# LPCB227_-_OVERVIEW.net
KiCad netlist of a schematic drawn in Altium Designer
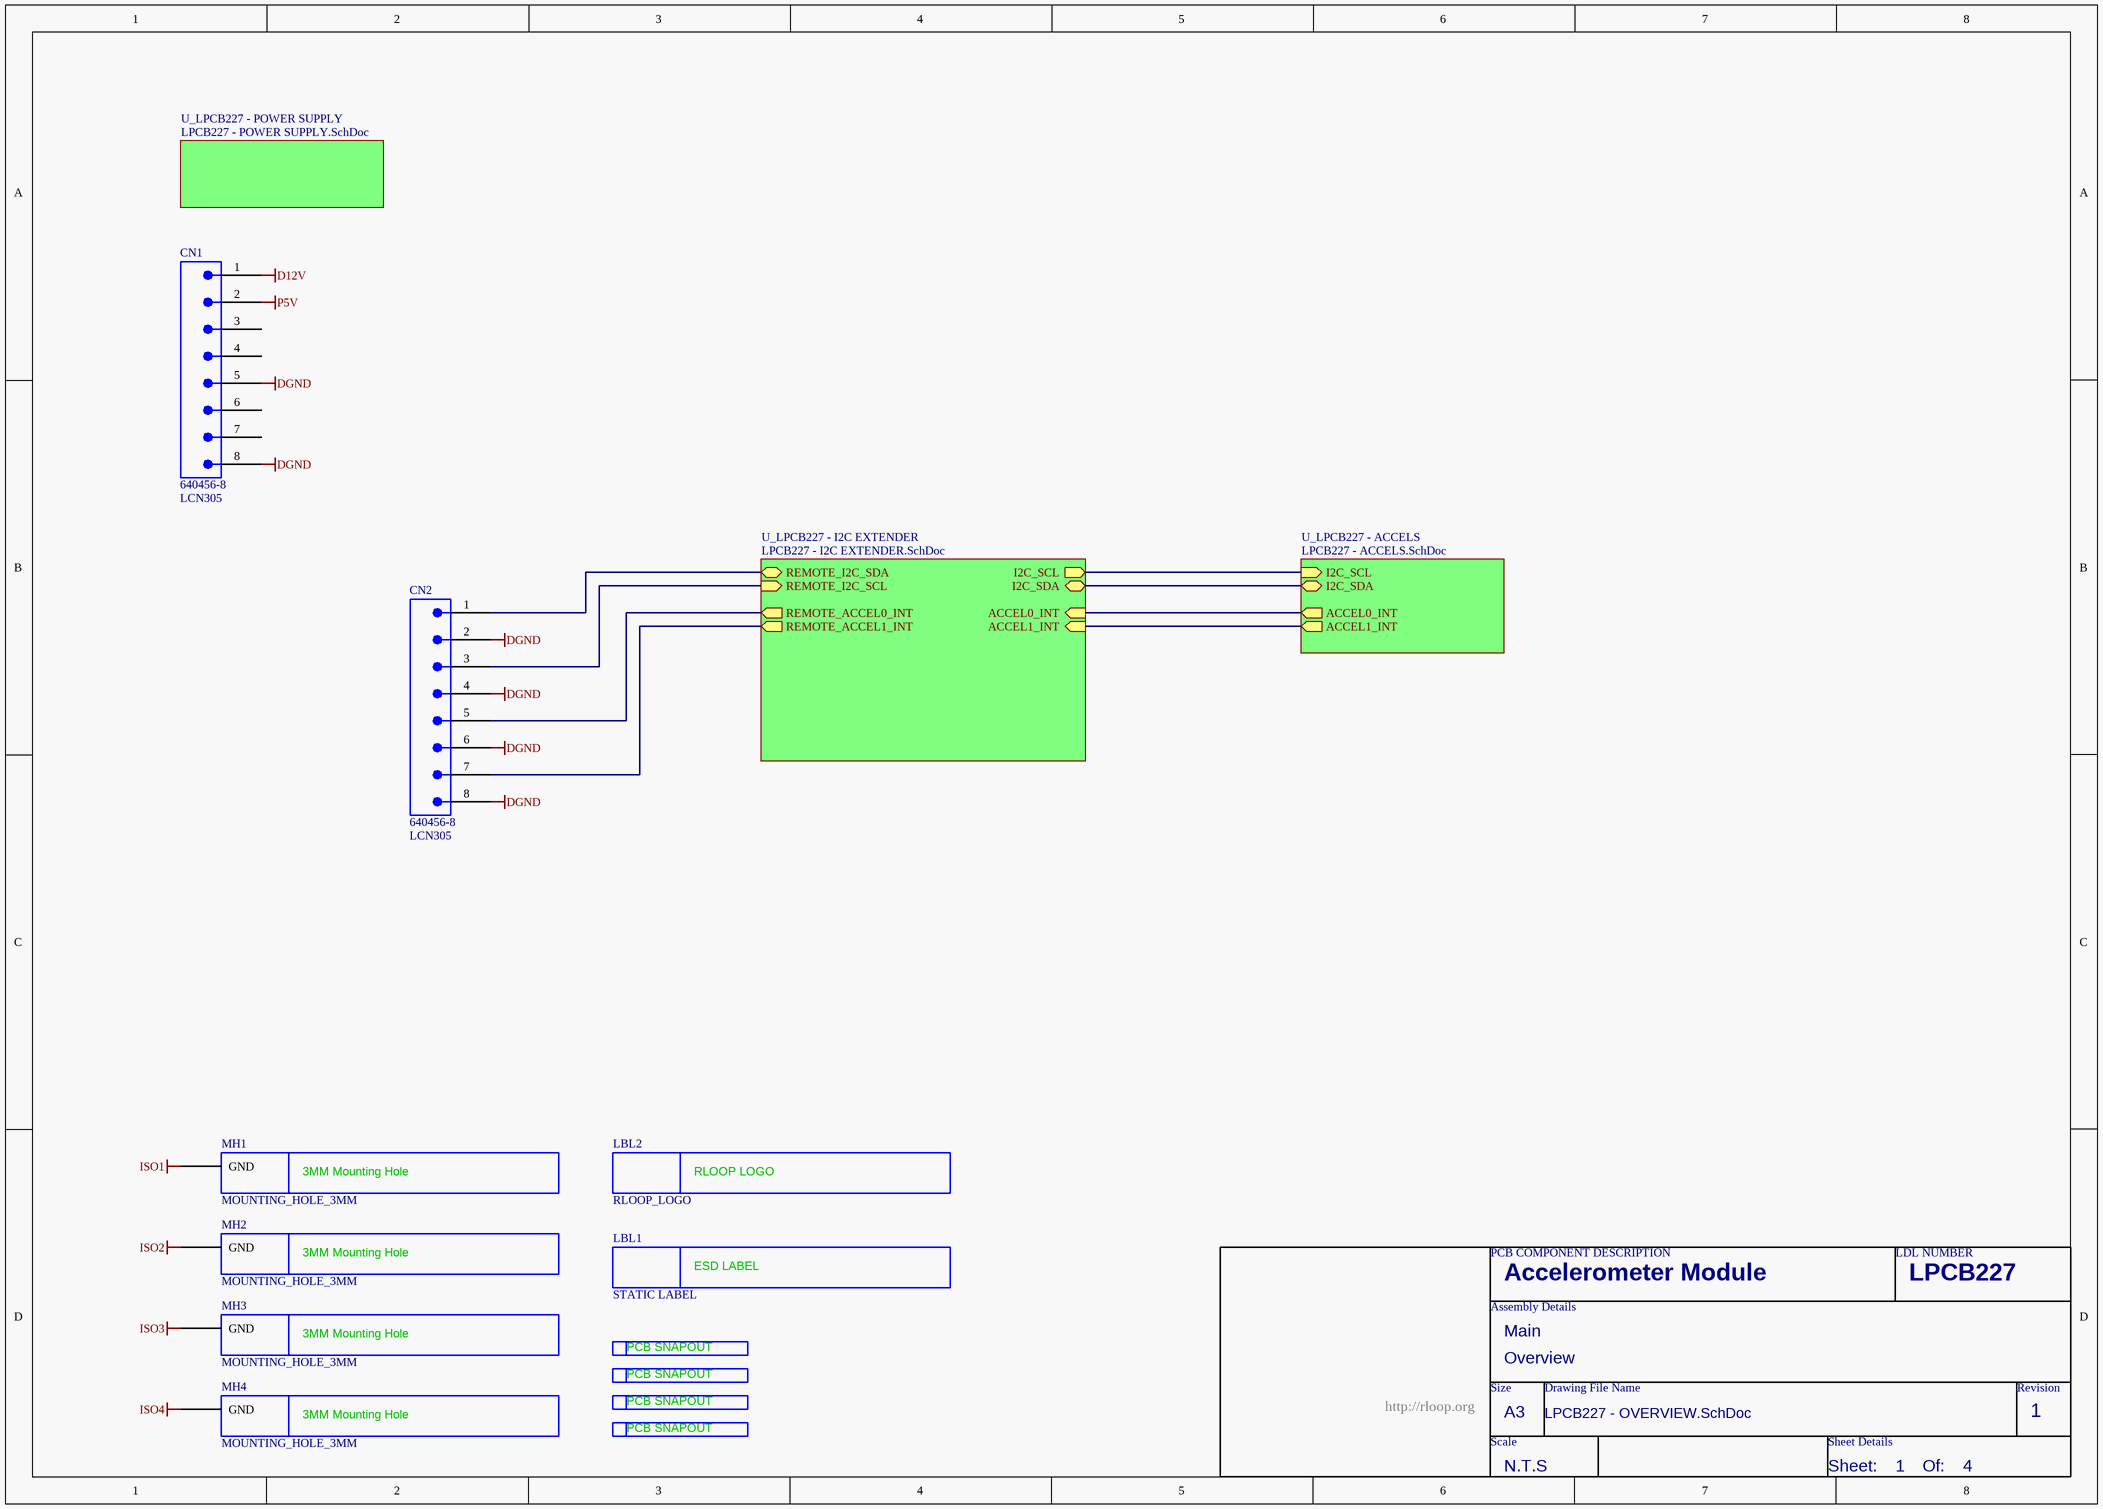
[diagram p0: LPCB227 - OVERVIEW.SchDoc]

(export (version "E")
  (design (tool "Eeschema 10.0.6"))
  (components
    (comp (ref "CN1")
      (value "640456-8")
      (footprint "640456-8")
      (description "Connector, Male Header, 8 Way")
      (fields (field (name "LDL_NUMBER") "LCN305"))
      (libsource (lib "LDL_Connectors") (part "640456-8"))
    )
    (comp (ref "CN2")
      (value "640456-8")
      (footprint "640456-8")
      (description "Connector, Male Header, 8 Way")
      (fields (field (name "LDL_NUMBER") "LCN305"))
      (libsource (lib "LDL_Connectors") (part "640456-8"))
    )
    (comp (ref "LBL1")
      (value "STATIC LABEL")
      (footprint "STATIC_LABEL")
      (libsource (lib "LDL_Mechanical") (part "STATIC LABEL"))
    )
    (comp (ref "LBL2")
      (value "RLOOP_LOGO")
      (footprint "RLOOP_LOGO")
      (libsource (lib "LDL_Mechanical") (part "RLOOP_LOGO"))
    )
    (comp (ref "MH1")
      (value "MOUNTING_HOLE_3MM")
      (footprint "MOUNTING_HOLE_3MM")
      (description "3MM Mouting Hole")
      (libsource (lib "LDL_Mechanical") (part "MOUNTING_HOLE_3MM"))
    )
    (comp (ref "MH2")
      (value "MOUNTING_HOLE_3MM")
      (footprint "MOUNTING_HOLE_3MM")
      (description "3MM Mouting Hole")
      (libsource (lib "LDL_Mechanical") (part "MOUNTING_HOLE_3MM"))
    )
    (comp (ref "MH3")
      (value "MOUNTING_HOLE_3MM")
      (footprint "MOUNTING_HOLE_3MM")
      (description "3MM Mouting Hole")
      (libsource (lib "LDL_Mechanical") (part "MOUNTING_HOLE_3MM"))
    )
    (comp (ref "MH4")
      (value "MOUNTING_HOLE_3MM")
      (footprint "MOUNTING_HOLE_3MM")
      (description "3MM Mouting Hole")
      (libsource (lib "LDL_Mechanical") (part "MOUNTING_HOLE_3MM"))
    )
    (comp (ref "SN1")
      (value "PCB_SNAPOUT")
      (footprint "SNAPOUT_NEW")
      (libsource (lib "LDL_Mechanical") (part "PCB_SNAPOUT"))
    )
    (comp (ref "SN2")
      (value "PCB_SNAPOUT")
      (footprint "SNAPOUT_NEW")
      (libsource (lib "LDL_Mechanical") (part "PCB_SNAPOUT"))
    )
    (comp (ref "SN3")
      (value "PCB_SNAPOUT")
      (footprint "SNAPOUT_NEW")
      (libsource (lib "LDL_Mechanical") (part "PCB_SNAPOUT"))
    )
    (comp (ref "SN4")
      (value "PCB_SNAPOUT")
      (footprint "SNAPOUT_NEW")
      (libsource (lib "LDL_Mechanical") (part "PCB_SNAPOUT"))
    )
  )
  (nets
    (net (code "5") (name "/REMOTE_ACCEL0_INT") (class "Default")
      (node (ref "CN2") (pin "5") (pinfunction "5_5") (pintype "passive"))
    )
    (net (code "6") (name "/REMOTE_ACCEL1_INT") (class "Default")
      (node (ref "CN2") (pin "7") (pinfunction "7_7") (pintype "passive"))
    )
    (net (code "7") (name "/REMOTE_I2C_SCL") (class "Default")
      (node (ref "CN2") (pin "3") (pinfunction "3_3") (pintype "passive"))
    )
    (net (code "8") (name "/REMOTE_I2C_SDA") (class "Default")
      (node (ref "CN2") (pin "1") (pinfunction "1_1") (pintype "passive"))
    )
    (net (code "9") (name "D12V") (class "Default")
      (node (ref "CN1") (pin "1") (pinfunction "1_1") (pintype "passive"))
    )
    (net (code "10") (name "DGND") (class "Default")
      (node (ref "CN1") (pin "5") (pinfunction "5_5") (pintype "passive"))
      (node (ref "CN1") (pin "8") (pinfunction "8_8") (pintype "passive"))
      (node (ref "CN2") (pin "2") (pinfunction "2_2") (pintype "passive"))
      (node (ref "CN2") (pin "4") (pinfunction "4_4") (pintype "passive"))
      (node (ref "CN2") (pin "6") (pinfunction "6_6") (pintype "passive"))
      (node (ref "CN2") (pin "8") (pinfunction "8_8") (pintype "passive"))
    )
    (net (code "11") (name "ISO1") (class "Default")
      (node (ref "MH1") (pin "MOUNT") (pinfunction "GND_MOUNT") (pintype "passive"))
    )
    (net (code "12") (name "ISO2") (class "Default")
      (node (ref "MH2") (pin "MOUNT") (pinfunction "GND_MOUNT") (pintype "passive"))
    )
    (net (code "13") (name "ISO3") (class "Default")
      (node (ref "MH3") (pin "MOUNT") (pinfunction "GND_MOUNT") (pintype "passive"))
    )
    (net (code "14") (name "ISO4") (class "Default")
      (node (ref "MH4") (pin "MOUNT") (pinfunction "GND_MOUNT") (pintype "passive"))
    )
    (net (code "15") (name "P5V") (class "Default")
      (node (ref "CN1") (pin "2") (pinfunction "2_2") (pintype "passive"))
    )
    (net (code "16") (name "unconnected-(CN1-Pad3)") (class "Default")
      (node (ref "CN1") (pin "3") (pinfunction "3_3") (pintype "passive"))
    )
    (net (code "17") (name "unconnected-(CN1-Pad4)") (class "Default")
      (node (ref "CN1") (pin "4") (pinfunction "4_4") (pintype "passive"))
    )
    (net (code "18") (name "unconnected-(CN1-Pad6)") (class "Default")
      (node (ref "CN1") (pin "6") (pinfunction "6_6") (pintype "passive"))
    )
    (net (code "19") (name "unconnected-(CN1-Pad7)") (class "Default")
      (node (ref "CN1") (pin "7") (pinfunction "7_7") (pintype "passive"))
    )
  )
)
